# USBHopper.net
KiCad netlist of a schematic drawn in EAGLE
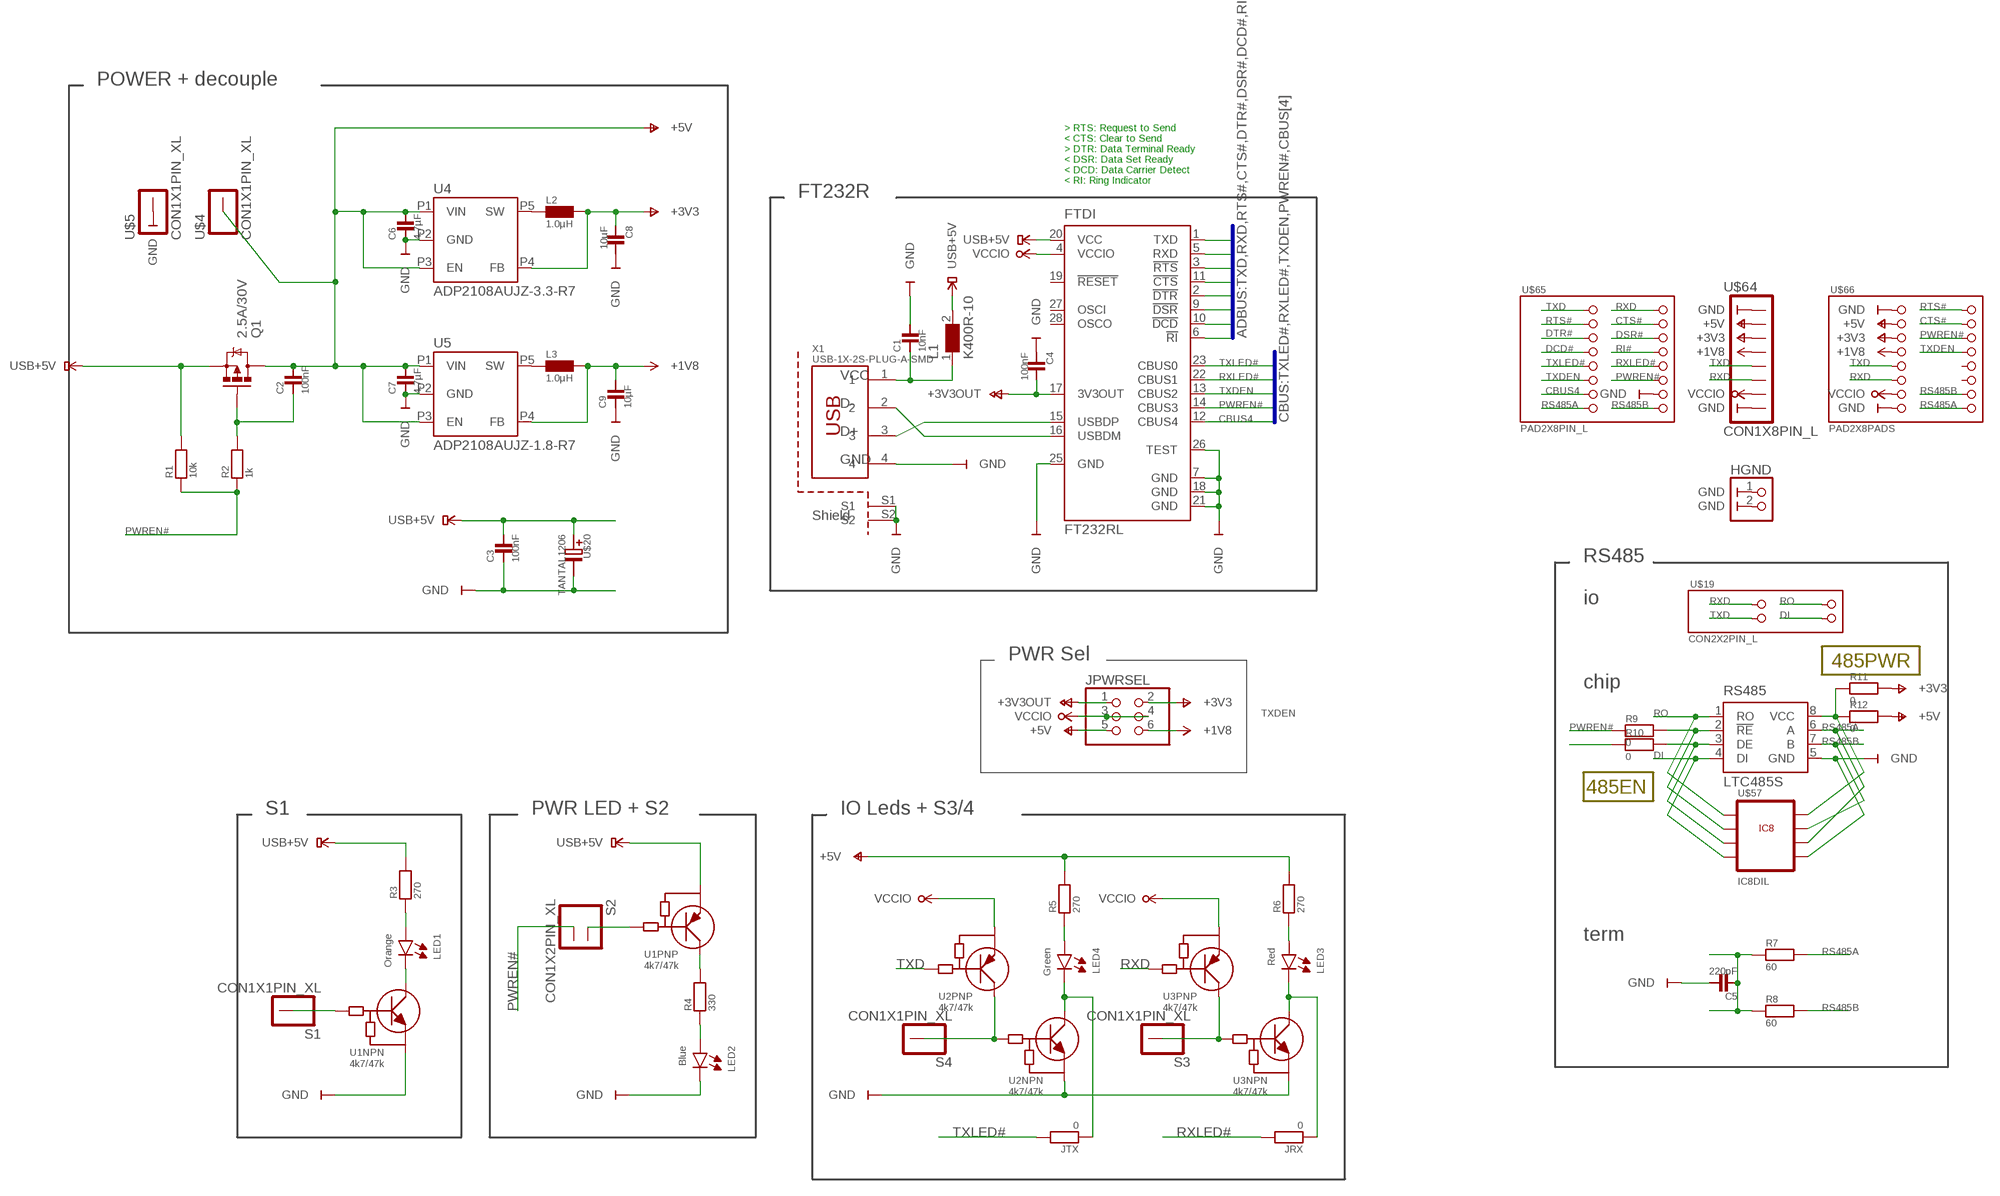
[diagram p0: schematic, sheet 1]

(export (version "E")
  (design (tool "Eeschema 10.0.6"))
  (components
    (comp (ref "C1")
      (value "10nF")
      (footprint "eagle-import:0805")
      (libsource (lib "eagle-import") (part "CAPACITOR"))
    )
    (comp (ref "C2")
      (value "100nF")
      (footprint "eagle-import:0805")
      (libsource (lib "eagle-import") (part "CAPACITOR"))
    )
    (comp (ref "C3")
      (value "100nF")
      (footprint "eagle-import:0805")
      (libsource (lib "eagle-import") (part "CAPACITOR"))
    )
    (comp (ref "C4")
      (value "100nF")
      (footprint "eagle-import:0805")
      (libsource (lib "eagle-import") (part "CAPACITOR"))
    )
    (comp (ref "C5")
      (value "220pF")
      (footprint "eagle-import:0805")
      (libsource (lib "eagle-import") (part "CAPACITOR"))
    )
    (comp (ref "C6")
      (value "4.7µF")
      (footprint "eagle-import:0805")
      (libsource (lib "eagle-import") (part "CAPACITOR"))
    )
    (comp (ref "C7")
      (value "4.7µF")
      (footprint "eagle-import:0805")
      (libsource (lib "eagle-import") (part "CAPACITOR"))
    )
    (comp (ref "C8")
      (value "10µF")
      (footprint "eagle-import:0805")
      (libsource (lib "eagle-import") (part "CAPACITOR"))
    )
    (comp (ref "C9")
      (value "10µF")
      (footprint "eagle-import:0805")
      (libsource (lib "eagle-import") (part "CAPACITOR"))
    )
    (comp (ref "FTDI")
      (value "FT232RL")
      (footprint "eagle-import:SSOP28_FLO")
      (libsource (lib "eagle-import") (part "FT232RL"))
    )
    (comp (ref "HGND")
      (value "PINHD-1X2")
      (footprint "eagle-import:1X02")
      (libsource (lib "eagle-import") (part "PINHD-1X2"))
    )
    (comp (ref "JPWRSEL")
      (value "PINHD-2X3")
      (footprint "eagle-import:2X03")
      (libsource (lib "eagle-import") (part "PINHD-2X3"))
    )
    (comp (ref "JRX")
      (value "0")
      (footprint "eagle-import:0805_CONNECT")
      (libsource (lib "eagle-import") (part "RESISTORCONNECT"))
    )
    (comp (ref "JTX")
      (value "0")
      (footprint "eagle-import:0805_CONNECT")
      (libsource (lib "eagle-import") (part "RESISTORCONNECT"))
    )
    (comp (ref "L1")
      (value "K400R-10")
      (footprint "eagle-import:0805")
      (libsource (lib "eagle-import") (part "WE-CBF_0805"))
    )
    (comp (ref "L2")
      (value "1.0µH")
      (footprint "eagle-import:0806")
      (libsource (lib "eagle-import") (part "INDUCTOR"))
    )
    (comp (ref "L3")
      (value "1.0µH")
      (footprint "eagle-import:0806")
      (libsource (lib "eagle-import") (part "INDUCTOR"))
    )
    (comp (ref "LED1")
      (value "Orange")
      (footprint "eagle-import:KPT-2012-E")
      (libsource (lib "eagle-import") (part "LEDKPT-2012-E"))
    )
    (comp (ref "LED2")
      (value "Blue")
      (footprint "eagle-import:KPT-2012-E")
      (libsource (lib "eagle-import") (part "LEDKPT-2012-E"))
    )
    (comp (ref "LED3")
      (value "Red")
      (footprint "eagle-import:KPT-2012-E")
      (libsource (lib "eagle-import") (part "LEDKPT-2012-E"))
    )
    (comp (ref "LED4")
      (value "Green")
      (footprint "eagle-import:KPT-2012-E")
      (libsource (lib "eagle-import") (part "LEDKPT-2012-E"))
    )
    (comp (ref "Q1")
      (value "2.5A/30V")
      (footprint "eagle-import:SOT23-3")
      (libsource (lib "eagle-import") (part "MOSFET-PCHANNELDMG2307L"))
    )
    (comp (ref "R1")
      (value "10k")
      (footprint "eagle-import:0805")
      (libsource (lib "eagle-import") (part "RESISTORWIDE"))
    )
    (comp (ref "R2")
      (value "1k")
      (footprint "eagle-import:0805")
      (libsource (lib "eagle-import") (part "RESISTORWIDE"))
    )
    (comp (ref "R3")
      (value "270")
      (footprint "eagle-import:0805")
      (libsource (lib "eagle-import") (part "RESISTORWIDE"))
    )
    (comp (ref "R4")
      (value "330")
      (footprint "eagle-import:0805")
      (libsource (lib "eagle-import") (part "RESISTORWIDE"))
    )
    (comp (ref "R5")
      (value "270")
      (footprint "eagle-import:0805")
      (libsource (lib "eagle-import") (part "RESISTORWIDE"))
    )
    (comp (ref "R6")
      (value "270")
      (footprint "eagle-import:0805")
      (libsource (lib "eagle-import") (part "RESISTORWIDE"))
    )
    (comp (ref "R7")
      (value "60")
      (footprint "eagle-import:0805")
      (libsource (lib "eagle-import") (part "RESISTORWIDE"))
    )
    (comp (ref "R8")
      (value "60")
      (footprint "eagle-import:0805_CONNECT")
      (libsource (lib "eagle-import") (part "RESISTORCONNECT"))
    )
    (comp (ref "R9")
      (value "0")
      (footprint "eagle-import:0805_CONNECT")
      (libsource (lib "eagle-import") (part "RESISTORCONNECT"))
    )
    (comp (ref "R10")
      (value "0")
      (footprint "eagle-import:0805_CONNECT")
      (libsource (lib "eagle-import") (part "RESISTORCONNECT"))
    )
    (comp (ref "R11")
      (value "0")
      (footprint "eagle-import:0805_CONNECT")
      (libsource (lib "eagle-import") (part "RESISTORCONNECT"))
    )
    (comp (ref "R12")
      (value "0")
      (footprint "eagle-import:0805_CONNECT")
      (libsource (lib "eagle-import") (part "RESISTORCONNECT"))
    )
    (comp (ref "RS485")
      (value "LTC485S")
      (footprint "eagle-import:SOIC8")
      (libsource (lib "eagle-import") (part "LTC485S"))
    )
    (comp (ref "S1")
      (value "CON1X1PIN_XL")
      (footprint "eagle-import:1X1PINS")
      (libsource (lib "eagle-import") (part "CON1X1PIN_XL"))
    )
    (comp (ref "S2")
      (value "CON1X2PIN_XL")
      (footprint "eagle-import:1X2PINS")
      (libsource (lib "eagle-import") (part "CON1X2PIN_XL"))
    )
    (comp (ref "S3")
      (value "CON1X1PIN_XL")
      (footprint "eagle-import:1X1PINS")
      (libsource (lib "eagle-import") (part "CON1X1PIN_XL"))
    )
    (comp (ref "S4")
      (value "CON1X1PIN_XL")
      (footprint "eagle-import:1X1PINS")
      (libsource (lib "eagle-import") (part "CON1X1PIN_XL"))
    )
    (comp (ref "U$4")
      (value "CON1X1PIN_XL")
      (footprint "eagle-import:1X1PINS")
      (libsource (lib "eagle-import") (part "CON1X1PIN_XL"))
    )
    (comp (ref "U$5")
      (value "CON1X1PIN_XL")
      (footprint "eagle-import:1X1PINS")
      (libsource (lib "eagle-import") (part "CON1X1PIN_XL"))
    )
    (comp (ref "U$19")
      (value "CON2X2PIN_L")
      (footprint "eagle-import:2X2PINS_L")
      (libsource (lib "eagle-import") (part "CON2X2PIN_L"))
    )
    (comp (ref "U$20")
      (value "TANTAL1206")
      (footprint "eagle-import:1206")
      (libsource (lib "eagle-import") (part "TANTAL1206"))
    )
    (comp (ref "U$57")
      (value "IC8DIL")
      (footprint "eagle-import:DIL8")
      (libsource (lib "eagle-import") (part "IC8DIL"))
    )
    (comp (ref "U$64")
      (value "CON1X8PIN_L")
      (footprint "eagle-import:1X8PINS_L")
      (libsource (lib "eagle-import") (part "CON1X8PIN_L"))
    )
    (comp (ref "U$65")
      (value "PAD2X8PIN_L")
      (footprint "eagle-import:2X8PINS_L")
      (libsource (lib "eagle-import") (part "PAD2X8PIN_L"))
    )
    (comp (ref "U$66")
      (value "PAD2X8PADS")
      (footprint "eagle-import:2X8PADS")
      (libsource (lib "eagle-import") (part "PAD2X8PADS"))
    )
    (comp (ref "U1")
      (value "4k7/47k")
      (footprint "eagle-import:SOT-457")
      (libsource (lib "eagle-import") (part "PNP_NPN_BIASNXP_PIMD3"))
    )
    (comp (ref "U2")
      (value "4k7/47k")
      (footprint "eagle-import:SOT-457")
      (libsource (lib "eagle-import") (part "PNP_NPN_BIASNXP_PIMD3"))
    )
    (comp (ref "U3")
      (value "4k7/47k")
      (footprint "eagle-import:SOT-457")
      (libsource (lib "eagle-import") (part "PNP_NPN_BIASNXP_PIMD3"))
    )
    (comp (ref "U4")
      (value "ADP2108AUJZ-3.3-R7")
      (footprint "eagle-import:SOT23")
      (libsource (lib "eagle-import") (part "DCDC"))
    )
    (comp (ref "U5")
      (value "ADP2108AUJZ-1.8-R7")
      (footprint "eagle-import:SOT23")
      (libsource (lib "eagle-import") (part "DCDC"))
    )
    (comp (ref "X1")
      (value "USB-1X-2S-PLUG-A-SMD")
      (footprint "eagle-import:USB-PLUG-A-SMD-2S")
      (libsource (lib "eagle-import") (part "USB-1X-2S-PLUG-A-SMD"))
    )
  )
  (nets
    (net (code "4") (name "+1V8") (class "Default")
      (node (ref "C9") (pin "P$2") (pinfunction "P$2_P$2") (pintype "bidirectional"))
      (node (ref "JPWRSEL") (pin "6") (pinfunction "6_6") (pintype "passive"))
      (node (ref "L3") (pin "P$1") (pinfunction "P$1_P$1") (pintype "bidirectional"))
      (node (ref "U$64") (pin "P$4") (pinfunction "P$4_P$4") (pintype "bidirectional"))
      (node (ref "U$66") (pin "P$7") (pinfunction "P$7_P$7") (pintype "bidirectional"))
      (node (ref "U5") (pin "P4") (pinfunction "FB_P4") (pintype "bidirectional"))
    )
    (net (code "5") (name "+3V3") (class "Default")
      (node (ref "C8") (pin "P$1") (pinfunction "P$1_P$1") (pintype "bidirectional"))
      (node (ref "JPWRSEL") (pin "2") (pinfunction "2_2") (pintype "passive"))
      (node (ref "L2") (pin "P$1") (pinfunction "P$1_P$1") (pintype "bidirectional"))
      (node (ref "R11") (pin "P$2") (pinfunction "P$2_P$2") (pintype "bidirectional"))
      (node (ref "U$64") (pin "P$3") (pinfunction "P$3_P$3") (pintype "bidirectional"))
      (node (ref "U$66") (pin "P$5") (pinfunction "P$5_P$5") (pintype "bidirectional"))
      (node (ref "U4") (pin "P4") (pinfunction "FB_P4") (pintype "bidirectional"))
    )
    (net (code "6") (name "+3V3OUT") (class "Default")
      (node (ref "C4") (pin "P$2") (pinfunction "P$2_P$2") (pintype "bidirectional"))
      (node (ref "FTDI") (pin "17") (pinfunction "3V3OUT_17") (pintype "output"))
      (node (ref "JPWRSEL") (pin "1") (pinfunction "1_1") (pintype "passive"))
    )
    (net (code "7") (name "+5V") (class "Default")
      (node (ref "C2") (pin "P$2") (pinfunction "P$2_P$2") (pintype "bidirectional"))
      (node (ref "C6") (pin "P$2") (pinfunction "P$2_P$2") (pintype "bidirectional"))
      (node (ref "C7") (pin "P$2") (pinfunction "P$2_P$2") (pintype "bidirectional"))
      (node (ref "JPWRSEL") (pin "5") (pinfunction "5_5") (pintype "passive"))
      (node (ref "Q1") (pin "3") (pinfunction "D_3") (pintype "passive"))
      (node (ref "R12") (pin "P$2") (pinfunction "P$2_P$2") (pintype "bidirectional"))
      (node (ref "R5") (pin "P$2") (pinfunction "P$2_P$2") (pintype "bidirectional"))
      (node (ref "R6") (pin "P$2") (pinfunction "P$2_P$2") (pintype "bidirectional"))
      (node (ref "U$4") (pin "P$1") (pinfunction "P$1_P$1") (pintype "bidirectional"))
      (node (ref "U$64") (pin "P$2") (pinfunction "P$2_P$2") (pintype "bidirectional"))
      (node (ref "U$66") (pin "P$3") (pinfunction "P$3_P$3") (pintype "bidirectional"))
      (node (ref "U4") (pin "P1") (pinfunction "VIN_P1") (pintype "bidirectional"))
      (node (ref "U4") (pin "P3") (pinfunction "EN_P3") (pintype "bidirectional"))
      (node (ref "U5") (pin "P1") (pinfunction "VIN_P1") (pintype "bidirectional"))
      (node (ref "U5") (pin "P3") (pinfunction "EN_P3") (pintype "bidirectional"))
    )
    (net (code "8") (name "/CBUS4") (class "Default")
      (node (ref "FTDI") (pin "12") (pinfunction "CBUS4_12") (pintype "bidirectional"))
      (node (ref "U$65") (pin "P$13") (pinfunction "P$13_P$13") (pintype "bidirectional"))
    )
    (net (code "9") (name "/CTS#") (class "Default")
      (node (ref "FTDI") (pin "11") (pinfunction "~{CTS}_11") (pintype "input"))
      (node (ref "U$65") (pin "P$4") (pinfunction "P$4_P$4") (pintype "bidirectional"))
      (node (ref "U$66") (pin "P$4") (pinfunction "P$4_P$4") (pintype "bidirectional"))
    )
    (net (code "10") (name "/DCD#") (class "Default")
      (node (ref "FTDI") (pin "10") (pinfunction "~{DCD}_10") (pintype "input"))
      (node (ref "U$65") (pin "P$7") (pinfunction "P$7_P$7") (pintype "bidirectional"))
    )
    (net (code "11") (name "/DI") (class "Default")
      (node (ref "RS485") (pin "4") (pinfunction "DI_4") (pintype "input"))
      (node (ref "U$19") (pin "P$4") (pinfunction "P$4_P$4") (pintype "bidirectional"))
      (node (ref "U$57") (pin "P$4") (pinfunction "P$4_P$4") (pintype "bidirectional"))
    )
    (net (code "12") (name "/DSR#") (class "Default")
      (node (ref "FTDI") (pin "9") (pinfunction "~{DSR}_9") (pintype "input"))
      (node (ref "U$65") (pin "P$6") (pinfunction "P$6_P$6") (pintype "bidirectional"))
    )
    (net (code "13") (name "/DTR#") (class "Default")
      (node (ref "FTDI") (pin "2") (pinfunction "~{DTR}_2") (pintype "output"))
      (node (ref "U$65") (pin "P$5") (pinfunction "P$5_P$5") (pintype "bidirectional"))
    )
    (net (code "14") (name "/PWREN#") (class "Default")
      (node (ref "FTDI") (pin "14") (pinfunction "CBUS3_14") (pintype "bidirectional"))
      (node (ref "R1") (pin "P$1") (pinfunction "P$1_P$1") (pintype "bidirectional"))
      (node (ref "R2") (pin "P$1") (pinfunction "P$1_P$1") (pintype "bidirectional"))
      (node (ref "R9") (pin "P$1") (pinfunction "P$1_P$1") (pintype "bidirectional"))
      (node (ref "S2") (pin "P$2") (pinfunction "P$2_P$2") (pintype "bidirectional"))
      (node (ref "U$65") (pin "P$12") (pinfunction "P$12_P$12") (pintype "bidirectional"))
      (node (ref "U$66") (pin "P$6") (pinfunction "P$6_P$6") (pintype "bidirectional"))
    )
    (net (code "15") (name "/RI#") (class "Default")
      (node (ref "FTDI") (pin "6") (pinfunction "~{RI}_6") (pintype "input"))
      (node (ref "U$65") (pin "P$8") (pinfunction "P$8_P$8") (pintype "bidirectional"))
    )
    (net (code "16") (name "/RO") (class "Default")
      (node (ref "RS485") (pin "1") (pinfunction "RO_1") (pintype "output"))
      (node (ref "U$19") (pin "P$2") (pinfunction "P$2_P$2") (pintype "bidirectional"))
      (node (ref "U$57") (pin "P$1") (pinfunction "P$1_P$1") (pintype "bidirectional"))
    )
    (net (code "17") (name "/RS485A") (class "Default")
      (node (ref "R7") (pin "P$2") (pinfunction "P$2_P$2") (pintype "bidirectional"))
      (node (ref "RS485") (pin "6") (pinfunction "A_6") (pintype "bidirectional"))
      (node (ref "U$57") (pin "P$6") (pinfunction "P$6_P$6") (pintype "bidirectional"))
      (node (ref "U$65") (pin "P$15") (pinfunction "P$15_P$15") (pintype "bidirectional"))
      (node (ref "U$66") (pin "P$16") (pinfunction "P$16_P$16") (pintype "bidirectional"))
    )
    (net (code "18") (name "/RS485B") (class "Default")
      (node (ref "R8") (pin "P$2") (pinfunction "P$2_P$2") (pintype "bidirectional"))
      (node (ref "RS485") (pin "7") (pinfunction "B_7") (pintype "bidirectional"))
      (node (ref "U$57") (pin "P$7") (pinfunction "P$7_P$7") (pintype "bidirectional"))
      (node (ref "U$65") (pin "P$16") (pinfunction "P$16_P$16") (pintype "bidirectional"))
      (node (ref "U$66") (pin "P$14") (pinfunction "P$14_P$14") (pintype "bidirectional"))
    )
    (net (code "19") (name "/RTS#") (class "Default")
      (node (ref "FTDI") (pin "3") (pinfunction "~{RTS}_3") (pintype "output"))
      (node (ref "U$65") (pin "P$3") (pinfunction "P$3_P$3") (pintype "bidirectional"))
      (node (ref "U$66") (pin "P$2") (pinfunction "P$2_P$2") (pintype "bidirectional"))
    )
    (net (code "20") (name "/RXD") (class "Default")
      (node (ref "FTDI") (pin "5") (pinfunction "RXD_5") (pintype "input"))
      (node (ref "U$19") (pin "P$1") (pinfunction "P$1_P$1") (pintype "bidirectional"))
      (node (ref "U$64") (pin "P$6") (pinfunction "P$6_P$6") (pintype "bidirectional"))
      (node (ref "U$65") (pin "P$2") (pinfunction "P$2_P$2") (pintype "bidirectional"))
      (node (ref "U$66") (pin "P$11") (pinfunction "P$11_P$11") (pintype "bidirectional"))
      (node (ref "U3") (pin "P$5") (pinfunction "B_P$5") (pintype "bidirectional"))
    )
    (net (code "21") (name "/RXLED#") (class "Default")
      (node (ref "FTDI") (pin "22") (pinfunction "CBUS1_22") (pintype "bidirectional"))
      (node (ref "JRX") (pin "P$2") (pinfunction "P$2_P$2") (pintype "bidirectional"))
      (node (ref "U$65") (pin "P$10") (pinfunction "P$10_P$10") (pintype "bidirectional"))
    )
    (net (code "22") (name "/TXD") (class "Default")
      (node (ref "FTDI") (pin "1") (pinfunction "TXD_1") (pintype "output"))
      (node (ref "U$19") (pin "P$3") (pinfunction "P$3_P$3") (pintype "bidirectional"))
      (node (ref "U$64") (pin "P$5") (pinfunction "P$5_P$5") (pintype "bidirectional"))
      (node (ref "U$65") (pin "P$1") (pinfunction "P$1_P$1") (pintype "bidirectional"))
      (node (ref "U$66") (pin "P$9") (pinfunction "P$9_P$9") (pintype "bidirectional"))
      (node (ref "U2") (pin "P$5") (pinfunction "B_P$5") (pintype "bidirectional"))
    )
    (net (code "23") (name "/TXDEN") (class "Default")
      (node (ref "FTDI") (pin "13") (pinfunction "CBUS2_13") (pintype "bidirectional"))
      (node (ref "R10") (pin "P$1") (pinfunction "P$1_P$1") (pintype "bidirectional"))
      (node (ref "U$65") (pin "P$11") (pinfunction "P$11_P$11") (pintype "bidirectional"))
      (node (ref "U$66") (pin "P$8") (pinfunction "P$8_P$8") (pintype "bidirectional"))
    )
    (net (code "24") (name "/TXLED#") (class "Default")
      (node (ref "FTDI") (pin "23") (pinfunction "CBUS0_23") (pintype "bidirectional"))
      (node (ref "JTX") (pin "P$2") (pinfunction "P$2_P$2") (pintype "bidirectional"))
      (node (ref "U$65") (pin "P$9") (pinfunction "P$9_P$9") (pintype "bidirectional"))
    )
    (net (code "27") (name "GND") (class "Default")
      (node (ref "C1") (pin "P$2") (pinfunction "P$2_P$2") (pintype "bidirectional"))
      (node (ref "C3") (pin "P$1") (pinfunction "P$1_P$1") (pintype "bidirectional"))
      (node (ref "C4") (pin "P$1") (pinfunction "P$1_P$1") (pintype "bidirectional"))
      (node (ref "C5") (pin "P$2") (pinfunction "P$2_P$2") (pintype "bidirectional"))
      (node (ref "C6") (pin "P$1") (pinfunction "P$1_P$1") (pintype "bidirectional"))
      (node (ref "C7") (pin "P$1") (pinfunction "P$1_P$1") (pintype "bidirectional"))
      (node (ref "C8") (pin "P$2") (pinfunction "P$2_P$2") (pintype "bidirectional"))
      (node (ref "C9") (pin "P$1") (pinfunction "P$1_P$1") (pintype "bidirectional"))
      (node (ref "FTDI") (pin "18") (pinfunction "GND_18") (pintype "power_in"))
      (node (ref "FTDI") (pin "21") (pinfunction "GND_21") (pintype "power_in"))
      (node (ref "FTDI") (pin "25") (pinfunction "GND_25") (pintype "power_in"))
      (node (ref "FTDI") (pin "26") (pinfunction "TEST_26") (pintype "input"))
      (node (ref "FTDI") (pin "7") (pinfunction "GND_7") (pintype "power_in"))
      (node (ref "HGND") (pin "1") (pinfunction "1_1") (pintype "passive"))
      (node (ref "HGND") (pin "2") (pinfunction "2_2") (pintype "passive"))
      (node (ref "LED2") (pin "2") (pinfunction "C$1_2") (pintype "bidirectional"))
      (node (ref "RS485") (pin "5") (pinfunction "GND_5") (pintype "input"))
      (node (ref "U$20") (pin "P$2") (pinfunction "P$2_P$2") (pintype "bidirectional"))
      (node (ref "U$5") (pin "P$1") (pinfunction "P$1_P$1") (pintype "bidirectional"))
      (node (ref "U$57") (pin "P$5") (pinfunction "P$5_P$5") (pintype "bidirectional"))
      (node (ref "U$64") (pin "P$1") (pinfunction "P$1_P$1") (pintype "bidirectional"))
      (node (ref "U$64") (pin "P$8") (pinfunction "P$8_P$8") (pintype "bidirectional"))
      (node (ref "U$65") (pin "P$14") (pinfunction "P$14_P$14") (pintype "bidirectional"))
      (node (ref "U$66") (pin "P$1") (pinfunction "P$1_P$1") (pintype "bidirectional"))
      (node (ref "U$66") (pin "P$15") (pinfunction "P$15_P$15") (pintype "bidirectional"))
      (node (ref "U1") (pin "P$1") (pinfunction "E_P$1") (pintype "bidirectional"))
      (node (ref "U2") (pin "P$1") (pinfunction "E_P$1") (pintype "bidirectional"))
      (node (ref "U3") (pin "P$1") (pinfunction "E_P$1") (pintype "bidirectional"))
      (node (ref "U4") (pin "P2") (pinfunction "GND_P2") (pintype "bidirectional"))
      (node (ref "U5") (pin "P2") (pinfunction "GND_P2") (pintype "bidirectional"))
      (node (ref "X1") (pin "4") (pinfunction "4_4") (pintype "passive"))
      (node (ref "X1") (pin "S1") (pinfunction "S1_S1") (pintype "passive"))
      (node (ref "X1") (pin "S2") (pinfunction "S2_S2") (pintype "passive"))
    )
    (net (code "28") (name "Net-(C1-PadP$1)") (class "Default")
      (node (ref "C1") (pin "P$1") (pinfunction "P$1_P$1") (pintype "bidirectional"))
      (node (ref "L1") (pin "1") (pinfunction "1_1") (pintype "passive"))
      (node (ref "X1") (pin "1") (pinfunction "1_1") (pintype "passive"))
    )
    (net (code "29") (name "Net-(C5-PadP$1)") (class "Default")
      (node (ref "C5") (pin "P$1") (pinfunction "P$1_P$1") (pintype "bidirectional"))
      (node (ref "R7") (pin "P$1") (pinfunction "P$1_P$1") (pintype "bidirectional"))
      (node (ref "R8") (pin "P$1") (pinfunction "P$1_P$1") (pintype "bidirectional"))
    )
    (net (code "30") (name "Net-(FTDI-USBDM)") (class "Default")
      (node (ref "FTDI") (pin "16") (pinfunction "USBDM_16") (pintype "bidirectional"))
      (node (ref "X1") (pin "2") (pinfunction "2_2") (pintype "passive"))
    )
    (net (code "31") (name "Net-(FTDI-USBDP)") (class "Default")
      (node (ref "FTDI") (pin "15") (pinfunction "USBDP_15") (pintype "bidirectional"))
      (node (ref "X1") (pin "3") (pinfunction "3_3") (pintype "passive"))
    )
    (net (code "32") (name "Net-(LED1-A$1)") (class "Default")
      (node (ref "LED1") (pin "1") (pinfunction "A$1_1") (pintype "bidirectional"))
      (node (ref "R3") (pin "P$1") (pinfunction "P$1_P$1") (pintype "bidirectional"))
    )
    (net (code "33") (name "Net-(LED1-C$1)") (class "Default")
      (node (ref "LED1") (pin "2") (pinfunction "C$1_2") (pintype "bidirectional"))
      (node (ref "U1") (pin "P$6") (pinfunction "C_P$6") (pintype "bidirectional"))
    )
    (net (code "34") (name "Net-(LED2-A$1)") (class "Default")
      (node (ref "LED2") (pin "1") (pinfunction "A$1_1") (pintype "bidirectional"))
      (node (ref "R4") (pin "P$1") (pinfunction "P$1_P$1") (pintype "bidirectional"))
    )
    (net (code "35") (name "Net-(LED3-A$1)") (class "Default")
      (node (ref "LED3") (pin "1") (pinfunction "A$1_1") (pintype "bidirectional"))
      (node (ref "R6") (pin "P$1") (pinfunction "P$1_P$1") (pintype "bidirectional"))
    )
    (net (code "36") (name "Net-(LED3-C$1)") (class "Default")
      (node (ref "JRX") (pin "P$1") (pinfunction "P$1_P$1") (pintype "bidirectional"))
      (node (ref "LED3") (pin "2") (pinfunction "C$1_2") (pintype "bidirectional"))
      (node (ref "U3") (pin "P$6") (pinfunction "C_P$6") (pintype "bidirectional"))
    )
    (net (code "37") (name "Net-(LED4-A$1)") (class "Default")
      (node (ref "LED4") (pin "1") (pinfunction "A$1_1") (pintype "bidirectional"))
      (node (ref "R5") (pin "P$1") (pinfunction "P$1_P$1") (pintype "bidirectional"))
    )
    (net (code "38") (name "Net-(LED4-C$1)") (class "Default")
      (node (ref "JTX") (pin "P$1") (pinfunction "P$1_P$1") (pintype "bidirectional"))
      (node (ref "LED4") (pin "2") (pinfunction "C$1_2") (pintype "bidirectional"))
      (node (ref "U2") (pin "P$6") (pinfunction "C_P$6") (pintype "bidirectional"))
    )
    (net (code "39") (name "Net-(Q1-G)") (class "Default")
      (node (ref "C2") (pin "P$1") (pinfunction "P$1_P$1") (pintype "bidirectional"))
      (node (ref "Q1") (pin "1") (pinfunction "G_1") (pintype "passive"))
      (node (ref "R2") (pin "P$2") (pinfunction "P$2_P$2") (pintype "bidirectional"))
    )
    (net (code "40") (name "Net-(RS485-DE)") (class "Default")
      (node (ref "R10") (pin "P$2") (pinfunction "P$2_P$2") (pintype "bidirectional"))
      (node (ref "RS485") (pin "3") (pinfunction "DE_3") (pintype "input"))
      (node (ref "U$57") (pin "P$3") (pinfunction "P$3_P$3") (pintype "bidirectional"))
    )
    (net (code "41") (name "Net-(RS485-VCC)") (class "Default")
      (node (ref "R11") (pin "P$1") (pinfunction "P$1_P$1") (pintype "bidirectional"))
      (node (ref "R12") (pin "P$1") (pinfunction "P$1_P$1") (pintype "bidirectional"))
      (node (ref "RS485") (pin "8") (pinfunction "VCC_8") (pintype "input"))
      (node (ref "U$57") (pin "P$8") (pinfunction "P$8_P$8") (pintype "bidirectional"))
    )
    (net (code "42") (name "Net-(RS485-~{RE})") (class "Default")
      (node (ref "R9") (pin "P$2") (pinfunction "P$2_P$2") (pintype "bidirectional"))
      (node (ref "RS485") (pin "2") (pinfunction "~{RE}_2") (pintype "input"))
      (node (ref "U$57") (pin "P$2") (pinfunction "P$2_P$2") (pintype "bidirectional"))
    )
    (net (code "43") (name "Net-(U1A-B)") (class "Default")
      (node (ref "S1") (pin "P$1") (pinfunction "P$1_P$1") (pintype "bidirectional"))
      (node (ref "U1") (pin "P$2") (pinfunction "B_P$2") (pintype "bidirectional"))
    )
    (net (code "44") (name "Net-(U1B-B)") (class "Default")
      (node (ref "S2") (pin "P$1") (pinfunction "P$1_P$1") (pintype "bidirectional"))
      (node (ref "U1") (pin "P$5") (pinfunction "B_P$5") (pintype "bidirectional"))
    )
    (net (code "45") (name "Net-(U1B-C)") (class "Default")
      (node (ref "R4") (pin "P$2") (pinfunction "P$2_P$2") (pintype "bidirectional"))
      (node (ref "U1") (pin "P$3") (pinfunction "C_P$3") (pintype "bidirectional"))
    )
    (net (code "46") (name "Net-(U2A-B)") (class "Default")
      (node (ref "S4") (pin "P$1") (pinfunction "P$1_P$1") (pintype "bidirectional"))
      (node (ref "U2") (pin "P$2") (pinfunction "B_P$2") (pintype "bidirectional"))
      (node (ref "U2") (pin "P$3") (pinfunction "C_P$3") (pintype "bidirectional"))
    )
    (net (code "47") (name "Net-(U3A-B)") (class "Default")
      (node (ref "S3") (pin "P$1") (pinfunction "P$1_P$1") (pintype "bidirectional"))
      (node (ref "U3") (pin "P$2") (pinfunction "B_P$2") (pintype "bidirectional"))
      (node (ref "U3") (pin "P$3") (pinfunction "C_P$3") (pintype "bidirectional"))
    )
    (net (code "48") (name "Net-(U4-SW)") (class "Default")
      (node (ref "L2") (pin "P$2") (pinfunction "P$2_P$2") (pintype "bidirectional"))
      (node (ref "U4") (pin "P5") (pinfunction "SW_P5") (pintype "bidirectional"))
    )
    (net (code "49") (name "Net-(U5-SW)") (class "Default")
      (node (ref "L3") (pin "P$2") (pinfunction "P$2_P$2") (pintype "bidirectional"))
      (node (ref "U5") (pin "P5") (pinfunction "SW_P5") (pintype "bidirectional"))
    )
    (net (code "50") (name "USB+5V") (class "Default")
      (node (ref "C3") (pin "P$2") (pinfunction "P$2_P$2") (pintype "bidirectional"))
      (node (ref "FTDI") (pin "20") (pinfunction "VCC_20") (pintype "power_in"))
      (node (ref "L1") (pin "2") (pinfunction "2_2") (pintype "passive"))
      (node (ref "Q1") (pin "2") (pinfunction "S_2") (pintype "passive"))
      (node (ref "R1") (pin "P$2") (pinfunction "P$2_P$2") (pintype "bidirectional"))
      (node (ref "R3") (pin "P$2") (pinfunction "P$2_P$2") (pintype "bidirectional"))
      (node (ref "U$20") (pin "P$1") (pinfunction "P$1_P$1") (pintype "bidirectional"))
      (node (ref "U1") (pin "P$4") (pinfunction "E_P$4") (pintype "bidirectional"))
    )
    (net (code "51") (name "VCCIO") (class "Default")
      (node (ref "FTDI") (pin "4") (pinfunction "VCCIO_4") (pintype "power_in"))
      (node (ref "JPWRSEL") (pin "3") (pinfunction "3_3") (pintype "passive"))
      (node (ref "JPWRSEL") (pin "4") (pinfunction "4_4") (pintype "passive"))
      (node (ref "U$64") (pin "P$7") (pinfunction "P$7_P$7") (pintype "bidirectional"))
      (node (ref "U$66") (pin "P$13") (pinfunction "P$13_P$13") (pintype "bidirectional"))
      (node (ref "U2") (pin "P$4") (pinfunction "E_P$4") (pintype "bidirectional"))
      (node (ref "U3") (pin "P$4") (pinfunction "E_P$4") (pintype "bidirectional"))
    )
    (net (code "52") (name "unconnected-(FTDI-OSCI-Pad27)") (class "Default")
      (node (ref "FTDI") (pin "27") (pinfunction "OSCI_27") (pintype "input"))
    )
    (net (code "53") (name "unconnected-(FTDI-OSCO-Pad28)") (class "Default")
      (node (ref "FTDI") (pin "28") (pinfunction "OSCO_28") (pintype "output"))
    )
    (net (code "54") (name "unconnected-(FTDI-~{RESET}-Pad19)") (class "Default")
      (node (ref "FTDI") (pin "19") (pinfunction "~{RESET}_19") (pintype "input"))
    )
    (net (code "55") (name "unconnected-(U$66-PadP$10)") (class "Default")
      (node (ref "U$66") (pin "P$10") (pinfunction "P$10_P$10") (pintype "bidirectional"))
    )
    (net (code "56") (name "unconnected-(U$66-PadP$12)") (class "Default")
      (node (ref "U$66") (pin "P$12") (pinfunction "P$12_P$12") (pintype "bidirectional"))
    )
  )
)
